# Gesture_Sensor_Card.net
KiCad netlist of a schematic drawn in EAGLE
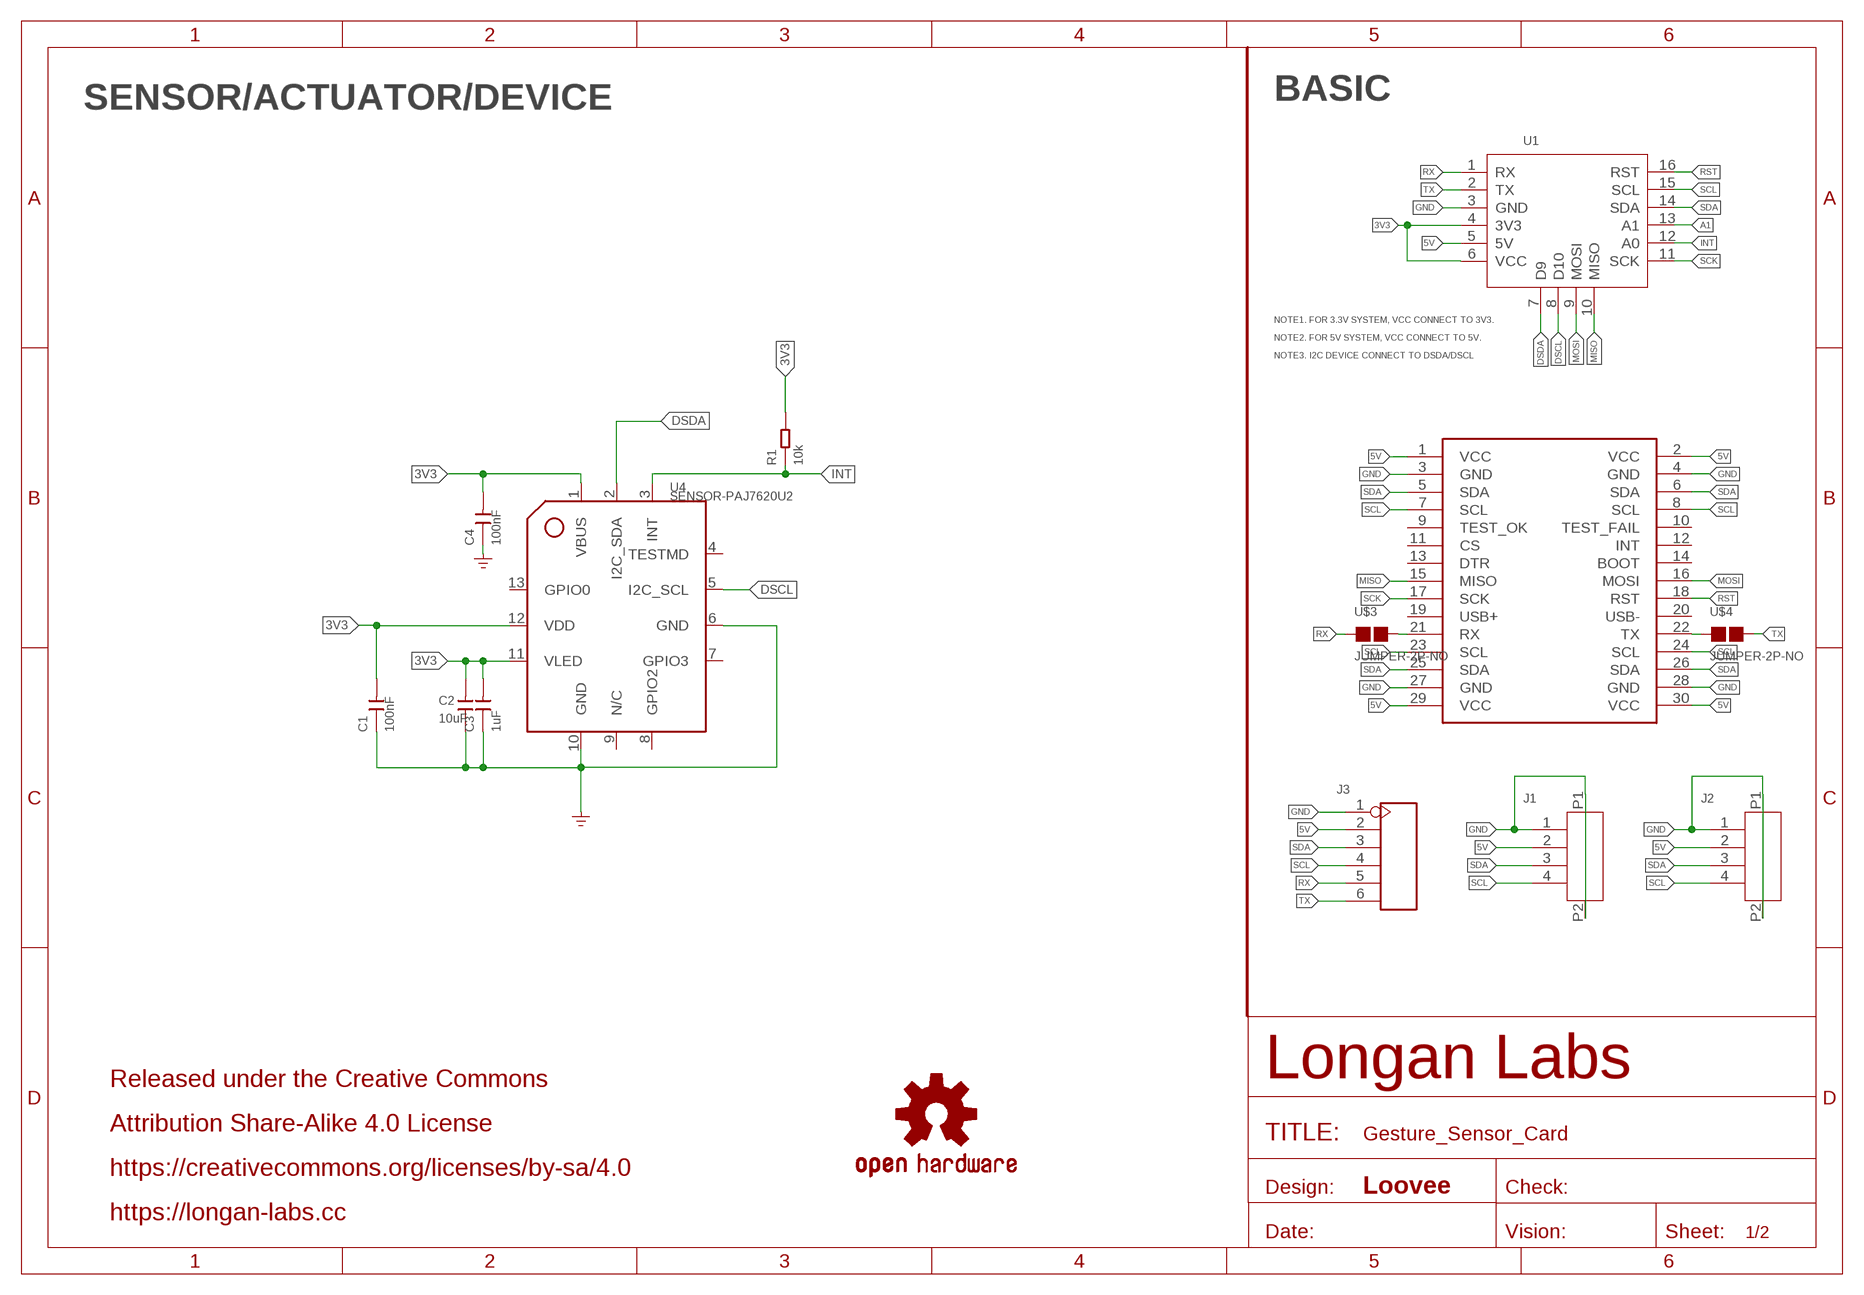
[diagram p0: schematic, sheet 1]

(export (version "E")
  (design (tool "Eeschema 10.0.6"))
  (components
    (comp (ref "C1")
      (value "100nF")
      (footprint "eagle-import:C0603")
      (libsource (lib "eagle-import") (part "CAP-0603"))
    )
    (comp (ref "C2")
      (value "10uF")
      (footprint "eagle-import:C0603")
      (libsource (lib "eagle-import") (part "CAP-0603"))
    )
    (comp (ref "C3")
      (value "1uF")
      (footprint "eagle-import:C0603")
      (libsource (lib "eagle-import") (part "CAP-0603"))
    )
    (comp (ref "C4")
      (value "100nF")
      (footprint "eagle-import:C0603")
      (libsource (lib "eagle-import") (part "CAP-0603"))
    )
    (comp (ref "J1")
      (value "HEADER-4P-1.0")
      (footprint "eagle-import:4P-1.0-90D")
      (libsource (lib "eagle-import") (part "HEADER-4P-1.0"))
    )
    (comp (ref "J2")
      (value "HEADER-4P-1.0")
      (footprint "eagle-import:4P-1.0-90D")
      (libsource (lib "eagle-import") (part "HEADER-4P-1.0"))
    )
    (comp (ref "J3")
      (value "HEADER-6P-55/35MIL")
      (footprint "eagle-import:H6-2.54")
      (libsource (lib "eagle-import") (part "HEADER-6P-55/35MIL"))
    )
    (comp (ref "LOGO2")
      (value "OSHW-LOGOS")
      (footprint "eagle-import:OSHW-LOGO-S")
      (libsource (lib "eagle-import") (part "OSHW-LOGOS"))
    )
    (comp (ref "MOUDLE1")
      (value "MOUDLE-2X15P-2.54'BOARD'")
      (footprint "eagle-import:MOUDLE-2X15P-2.54")
      (libsource (lib "eagle-import") (part "MOUDLE-2X15P-2.54'BOARD'"))
    )
    (comp (ref "R1")
      (value "10k")
      (footprint "eagle-import:R0603")
      (libsource (lib "eagle-import") (part "RES-0603"))
    )
    (comp (ref "U$3")
      (value "JUMPER-2P-NO")
      (footprint "eagle-import:2P-SMD-NO")
      (libsource (lib "eagle-import") (part "JUMPER-2P-NO"))
    )
    (comp (ref "U$4")
      (value "JUMPER-2P-NO")
      (footprint "eagle-import:2P-SMD-NO")
      (libsource (lib "eagle-import") (part "JUMPER-2P-NO"))
    )
    (comp (ref "U1")
      (value "MOUDLE-CARDS")
      (footprint "eagle-import:16P-2.0-CARDS")
      (libsource (lib "eagle-import") (part "MOUDLE-CARDS"))
    )
    (comp (ref "U4")
      (value "SENSOR-PAJ7620U2")
      (footprint "eagle-import:LGA13-SMD-L5.2_W3_H2MM")
      (libsource (lib "eagle-import") (part "SENSOR-PAJ7620U2"))
    )
  )
  (nets
    (net (code "1") (name "3V3") (class "Default")
      (node (ref "C1") (pin "2") (pinfunction "2_2") (pintype "passive"))
      (node (ref "C2") (pin "2") (pinfunction "2_2") (pintype "passive"))
      (node (ref "C3") (pin "2") (pinfunction "2_2") (pintype "passive"))
      (node (ref "C4") (pin "2") (pinfunction "2_2") (pintype "passive"))
      (node (ref "R1") (pin "2") (pinfunction "2_2") (pintype "passive"))
      (node (ref "U1") (pin "4") (pinfunction "3V3_4") (pintype "bidirectional"))
      (node (ref "U1") (pin "6") (pinfunction "VCC_6") (pintype "bidirectional"))
      (node (ref "U4") (pin "1") (pinfunction "VBUS_1") (pintype "bidirectional"))
      (node (ref "U4") (pin "11") (pinfunction "VLED_11") (pintype "bidirectional"))
      (node (ref "U4") (pin "12") (pinfunction "VDD_12") (pintype "bidirectional"))
    )
    (net (code "2") (name "5V") (class "Default")
      (node (ref "J1") (pin "2") (pinfunction "2_2") (pintype "bidirectional"))
      (node (ref "J2") (pin "2") (pinfunction "2_2") (pintype "bidirectional"))
      (node (ref "J3") (pin "2") (pinfunction "2_2") (pintype "bidirectional"))
      (node (ref "MOUDLE1") (pin "1") (pinfunction "VCC_1") (pintype "bidirectional"))
      (node (ref "MOUDLE1") (pin "2") (pinfunction "VCC_2") (pintype "bidirectional"))
      (node (ref "MOUDLE1") (pin "29") (pinfunction "VCC_29") (pintype "bidirectional"))
      (node (ref "MOUDLE1") (pin "30") (pinfunction "VCC_30") (pintype "bidirectional"))
      (node (ref "U1") (pin "5") (pinfunction "5V_5") (pintype "bidirectional"))
    )
    (net (code "3") (name "A1") (class "Default")
      (node (ref "U1") (pin "13") (pinfunction "A1_13") (pintype "bidirectional"))
    )
    (net (code "4") (name "DSCL") (class "Default")
      (node (ref "U1") (pin "8") (pinfunction "D10_8") (pintype "bidirectional"))
      (node (ref "U4") (pin "5") (pinfunction "I2C_SCL_5") (pintype "bidirectional"))
    )
    (net (code "5") (name "DSDA") (class "Default")
      (node (ref "U1") (pin "7") (pinfunction "D9_7") (pintype "bidirectional"))
      (node (ref "U4") (pin "2") (pinfunction "I2C_SDA_2") (pintype "bidirectional"))
    )
    (net (code "6") (name "GND") (class "Default")
      (node (ref "C1") (pin "1") (pinfunction "1_1") (pintype "passive"))
      (node (ref "C2") (pin "1") (pinfunction "1_1") (pintype "passive"))
      (node (ref "C3") (pin "1") (pinfunction "1_1") (pintype "passive"))
      (node (ref "C4") (pin "1") (pinfunction "1_1") (pintype "passive"))
      (node (ref "J1") (pin "1") (pinfunction "1_1") (pintype "bidirectional"))
      (node (ref "J1") (pin "P1") (pinfunction "P1_P1") (pintype "bidirectional"))
      (node (ref "J1") (pin "P2") (pinfunction "P2_P2") (pintype "bidirectional"))
      (node (ref "J2") (pin "1") (pinfunction "1_1") (pintype "bidirectional"))
      (node (ref "J2") (pin "P1") (pinfunction "P1_P1") (pintype "bidirectional"))
      (node (ref "J2") (pin "P2") (pinfunction "P2_P2") (pintype "bidirectional"))
      (node (ref "J3") (pin "1") (pinfunction "1_1") (pintype "bidirectional"))
      (node (ref "MOUDLE1") (pin "27") (pinfunction "GND_27") (pintype "bidirectional"))
      (node (ref "MOUDLE1") (pin "28") (pinfunction "GND_28") (pintype "bidirectional"))
      (node (ref "MOUDLE1") (pin "3") (pinfunction "GND_3") (pintype "bidirectional"))
      (node (ref "MOUDLE1") (pin "4") (pinfunction "GND_4") (pintype "bidirectional"))
      (node (ref "U1") (pin "3") (pinfunction "GND_3") (pintype "bidirectional"))
      (node (ref "U4") (pin "10") (pinfunction "GND_10") (pintype "bidirectional"))
      (node (ref "U4") (pin "6") (pinfunction "GND_6") (pintype "bidirectional"))
    )
    (net (code "7") (name "INT") (class "Default")
      (node (ref "R1") (pin "1") (pinfunction "1_1") (pintype "passive"))
      (node (ref "U1") (pin "12") (pinfunction "A0_12") (pintype "bidirectional"))
      (node (ref "U4") (pin "3") (pinfunction "INT_3") (pintype "bidirectional"))
    )
    (net (code "8") (name "MISO") (class "Default")
      (node (ref "MOUDLE1") (pin "15") (pinfunction "MISO_15") (pintype "bidirectional"))
      (node (ref "U1") (pin "10") (pinfunction "MISO_10") (pintype "bidirectional"))
    )
    (net (code "9") (name "MOSI") (class "Default")
      (node (ref "MOUDLE1") (pin "16") (pinfunction "MOSI_16") (pintype "bidirectional"))
      (node (ref "U1") (pin "9") (pinfunction "MOSI_9") (pintype "bidirectional"))
    )
    (net (code "10") (name "Net-(MOUDLE1-RX)") (class "Default")
      (node (ref "MOUDLE1") (pin "21") (pinfunction "RX_21") (pintype "bidirectional"))
      (node (ref "U$3") (pin "2") (pinfunction "2_2") (pintype "bidirectional"))
    )
    (net (code "11") (name "Net-(MOUDLE1-TX)") (class "Default")
      (node (ref "MOUDLE1") (pin "22") (pinfunction "TX_22") (pintype "bidirectional"))
      (node (ref "U$4") (pin "1") (pinfunction "1_1") (pintype "bidirectional"))
    )
    (net (code "12") (name "RST") (class "Default")
      (node (ref "MOUDLE1") (pin "18") (pinfunction "RST_18") (pintype "bidirectional"))
      (node (ref "U1") (pin "16") (pinfunction "RST_16") (pintype "bidirectional"))
    )
    (net (code "13") (name "RX") (class "Default")
      (node (ref "J3") (pin "5") (pinfunction "5_5") (pintype "bidirectional"))
      (node (ref "U$3") (pin "1") (pinfunction "1_1") (pintype "bidirectional"))
      (node (ref "U1") (pin "1") (pinfunction "RX_1") (pintype "bidirectional"))
    )
    (net (code "14") (name "SCK") (class "Default")
      (node (ref "MOUDLE1") (pin "17") (pinfunction "SCK_17") (pintype "bidirectional"))
      (node (ref "U1") (pin "11") (pinfunction "SCK_11") (pintype "bidirectional"))
    )
    (net (code "15") (name "SCL") (class "Default")
      (node (ref "J1") (pin "4") (pinfunction "4_4") (pintype "bidirectional"))
      (node (ref "J2") (pin "4") (pinfunction "4_4") (pintype "bidirectional"))
      (node (ref "J3") (pin "4") (pinfunction "4_4") (pintype "bidirectional"))
      (node (ref "MOUDLE1") (pin "23") (pinfunction "SCL_23") (pintype "bidirectional"))
      (node (ref "MOUDLE1") (pin "24") (pinfunction "SCL_24") (pintype "bidirectional"))
      (node (ref "MOUDLE1") (pin "7") (pinfunction "SCL_7") (pintype "bidirectional"))
      (node (ref "MOUDLE1") (pin "8") (pinfunction "SCL_8") (pintype "bidirectional"))
      (node (ref "U1") (pin "15") (pinfunction "SCL_15") (pintype "bidirectional"))
    )
    (net (code "16") (name "SDA") (class "Default")
      (node (ref "J1") (pin "3") (pinfunction "3_3") (pintype "bidirectional"))
      (node (ref "J2") (pin "3") (pinfunction "3_3") (pintype "bidirectional"))
      (node (ref "J3") (pin "3") (pinfunction "3_3") (pintype "bidirectional"))
      (node (ref "MOUDLE1") (pin "25") (pinfunction "SDA_25") (pintype "bidirectional"))
      (node (ref "MOUDLE1") (pin "26") (pinfunction "SDA_26") (pintype "bidirectional"))
      (node (ref "MOUDLE1") (pin "5") (pinfunction "SDA_5") (pintype "bidirectional"))
      (node (ref "MOUDLE1") (pin "6") (pinfunction "SDA_6") (pintype "bidirectional"))
      (node (ref "U1") (pin "14") (pinfunction "SDA_14") (pintype "bidirectional"))
    )
    (net (code "17") (name "TX") (class "Default")
      (node (ref "J3") (pin "6") (pinfunction "6_6") (pintype "bidirectional"))
      (node (ref "U$4") (pin "2") (pinfunction "2_2") (pintype "bidirectional"))
      (node (ref "U1") (pin "2") (pinfunction "TX_2") (pintype "bidirectional"))
    )
    (net (code "18") (name "unconnected-(MOUDLE1-BOOT-Pad14)") (class "Default")
      (node (ref "MOUDLE1") (pin "14") (pinfunction "BOOT_14") (pintype "bidirectional"))
    )
    (net (code "19") (name "unconnected-(MOUDLE1-CS-Pad11)") (class "Default")
      (node (ref "MOUDLE1") (pin "11") (pinfunction "CS_11") (pintype "bidirectional"))
    )
    (net (code "20") (name "unconnected-(MOUDLE1-DTR-Pad13)") (class "Default")
      (node (ref "MOUDLE1") (pin "13") (pinfunction "DTR_13") (pintype "bidirectional"))
    )
    (net (code "21") (name "unconnected-(MOUDLE1-INT-Pad12)") (class "Default")
      (node (ref "MOUDLE1") (pin "12") (pinfunction "INT_12") (pintype "bidirectional"))
    )
    (net (code "22") (name "unconnected-(MOUDLE1-TEST_FAIL-Pad10)") (class "Default")
      (node (ref "MOUDLE1") (pin "10") (pinfunction "TEST_FAIL_10") (pintype "bidirectional"))
    )
    (net (code "23") (name "unconnected-(MOUDLE1-TEST_OK-Pad9)") (class "Default")
      (node (ref "MOUDLE1") (pin "9") (pinfunction "TEST_OK_9") (pintype "bidirectional"))
    )
    (net (code "24") (name "unconnected-(MOUDLE1-USB+-Pad19)") (class "Default")
      (node (ref "MOUDLE1") (pin "19") (pinfunction "USB+_19") (pintype "bidirectional"))
    )
    (net (code "25") (name "unconnected-(MOUDLE1-USB--Pad20)") (class "Default")
      (node (ref "MOUDLE1") (pin "20") (pinfunction "USB-_20") (pintype "bidirectional"))
    )
    (net (code "26") (name "unconnected-(U4-GPIO0-Pad13)") (class "Default")
      (node (ref "U4") (pin "13") (pinfunction "GPIO0_13") (pintype "bidirectional"))
    )
    (net (code "27") (name "unconnected-(U4-GPIO2-Pad8)") (class "Default")
      (node (ref "U4") (pin "8") (pinfunction "GPIO2_8") (pintype "bidirectional"))
    )
    (net (code "28") (name "unconnected-(U4-GPIO3-Pad7)") (class "Default")
      (node (ref "U4") (pin "7") (pinfunction "GPIO3_7") (pintype "bidirectional"))
    )
    (net (code "29") (name "unconnected-(U4-N{slash}C-Pad9)") (class "Default")
      (node (ref "U4") (pin "9") (pinfunction "N/C_9") (pintype "bidirectional"))
    )
    (net (code "30") (name "unconnected-(U4-TESTMD-Pad4)") (class "Default")
      (node (ref "U4") (pin "4") (pinfunction "TESTMD_4") (pintype "bidirectional"))
    )
  )
)
